# astable_555_timer_phase_1.net
KiCad netlist of a schematic drawn in EAGLE
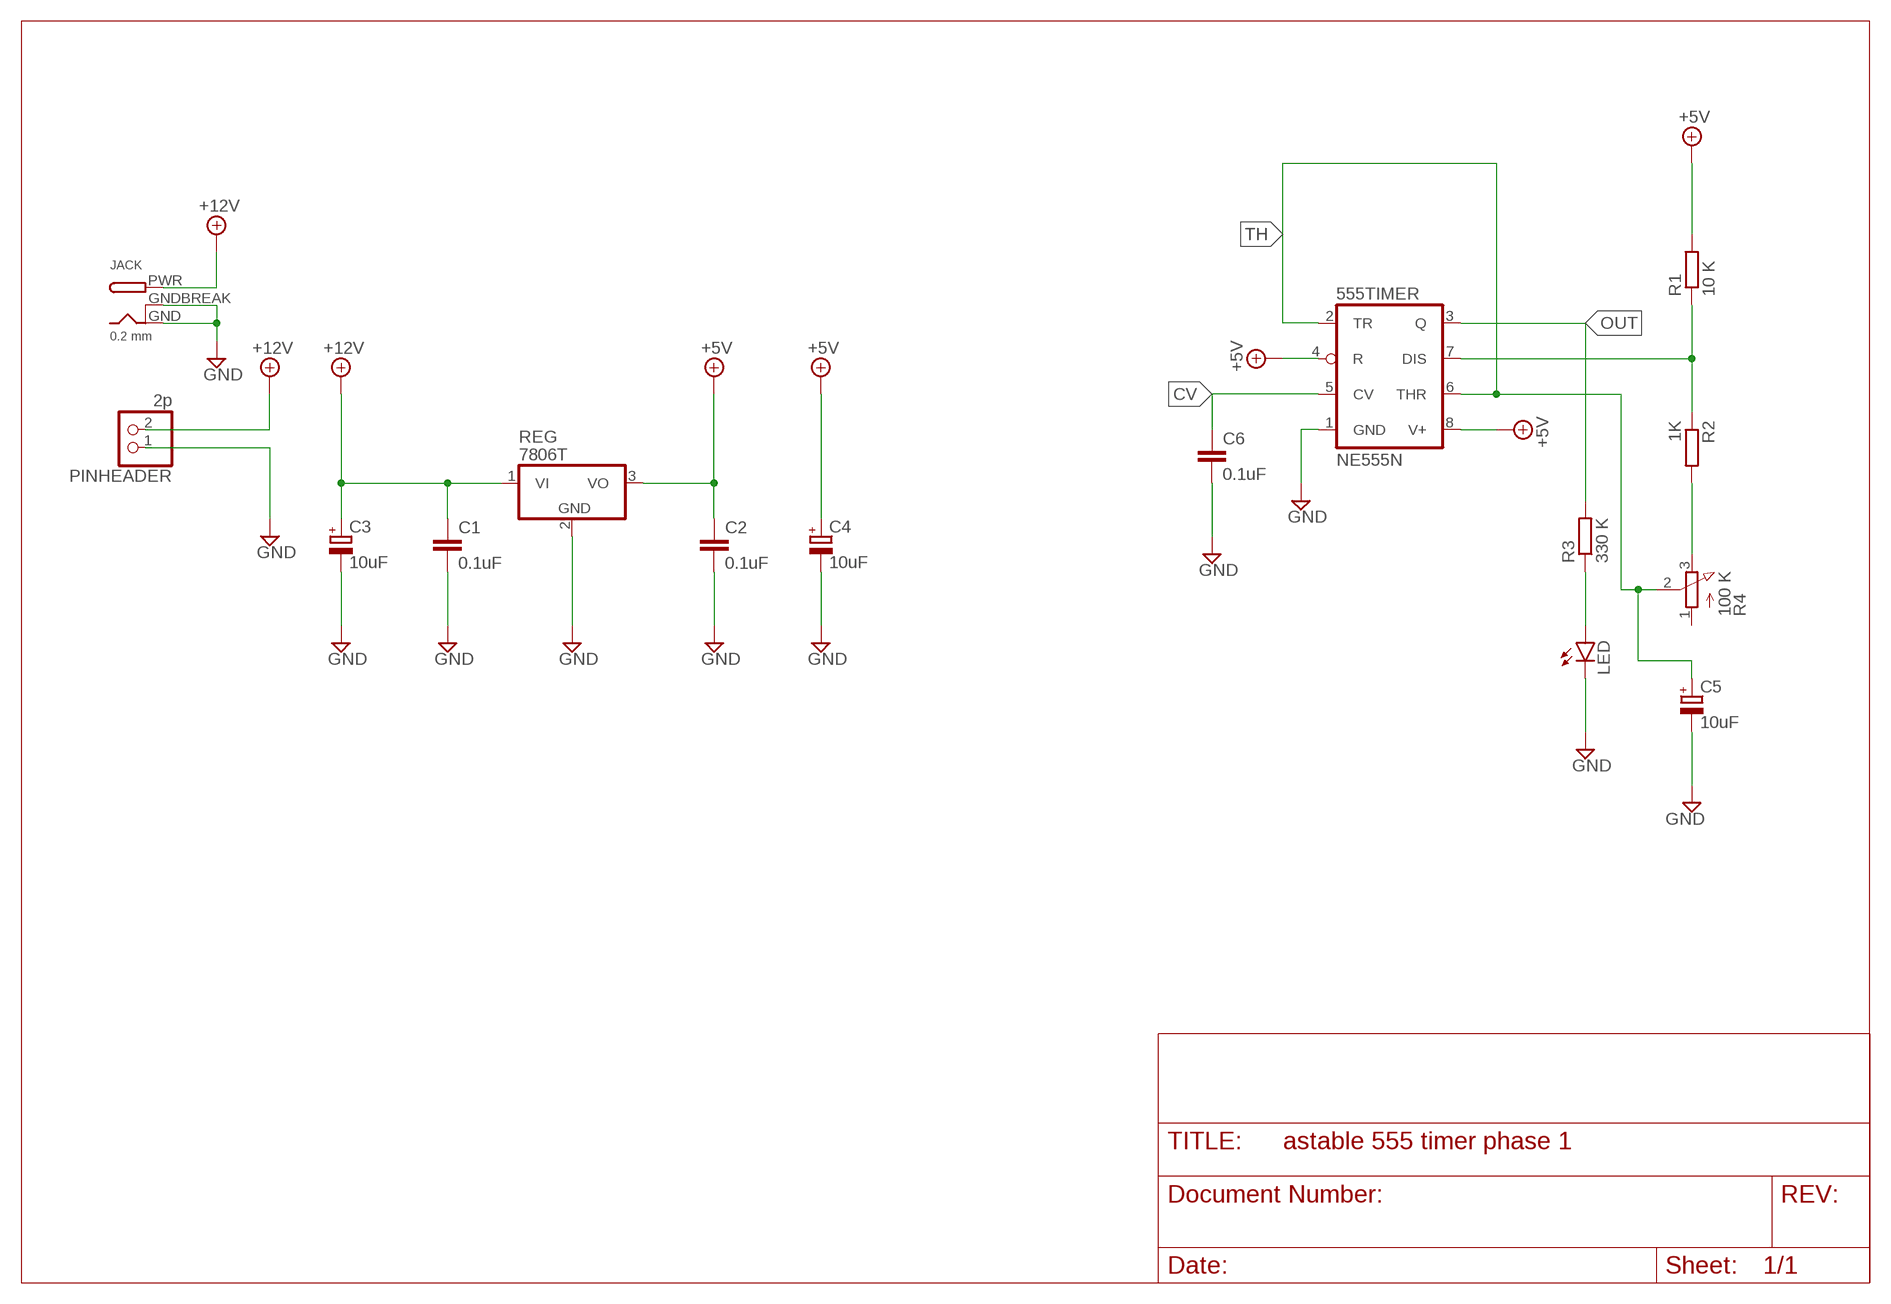
[diagram p0: schematic, sheet 1]

(export (version "E")
  (design (tool "Eeschema 10.0.6"))
  (components
    (comp (ref "555TIMER")
      (value "NE555N")
      (footprint "eagle-import:DIL08")
      (libsource (lib "eagle-import") (part "555NNE"))
    )
    (comp (ref "C1")
      (value "0.1uF")
      (footprint "eagle-import:C050-030X075")
      (libsource (lib "eagle-import") (part "C-EU050-030X075"))
    )
    (comp (ref "C2")
      (value "0.1uF")
      (footprint "eagle-import:C050-030X075")
      (libsource (lib "eagle-import") (part "C-EU050-030X075"))
    )
    (comp (ref "C3")
      (value "10uF")
      (footprint "eagle-import:E3,5-8")
      (libsource (lib "eagle-import") (part "CPOL-EUE3.5-8"))
    )
    (comp (ref "C4")
      (value "10uF")
      (footprint "eagle-import:E3,5-8")
      (libsource (lib "eagle-import") (part "CPOL-EUE3.5-8"))
    )
    (comp (ref "C5")
      (value "10uF")
      (footprint "eagle-import:E3,5-8")
      (libsource (lib "eagle-import") (part "CPOL-EUE3.5-8"))
    )
    (comp (ref "C6")
      (value "0.1uF")
      (footprint "eagle-import:C050-030X075")
      (libsource (lib "eagle-import") (part "C-EU050-030X075"))
    )
    (comp (ref "JACK")
      (value "0.2 mm")
      (footprint "eagle-import:DCJACK_2MM_PTH")
      (libsource (lib "eagle-import") (part "DCBARRELPTH"))
    )
    (comp (ref "LED")
      (value "LED5MM")
      (footprint "eagle-import:LED5MM")
      (libsource (lib "eagle-import") (part "LED5MM"))
    )
    (comp (ref "PINHEADER")
      (value "2p")
      (footprint "eagle-import:1X02")
      (libsource (lib "eagle-import") (part "PINHD-1X2"))
    )
    (comp (ref "R1")
      (value "10 K")
      (footprint "eagle-import:0207_10")
      (libsource (lib "eagle-import") (part "R-EU_0207/10"))
    )
    (comp (ref "R2")
      (value "1K")
      (footprint "eagle-import:0207_10")
      (libsource (lib "eagle-import") (part "R-EU_0207/10"))
    )
    (comp (ref "R3")
      (value "330 K")
      (footprint "eagle-import:0207_10")
      (libsource (lib "eagle-import") (part "R-EU_0207/10"))
    )
    (comp (ref "R4")
      (value "100 K")
      (footprint "eagle-import:3RP_1610N")
      (libsource (lib "eagle-import") (part "3RP/1610N"))
    )
    (comp (ref "REG")
      (value "7806T")
      (footprint "eagle-import:TO220H")
      (libsource (lib "eagle-import") (part "78T06"))
    )
  )
  (nets
    (net (code "1") (name "+5V") (class "Default")
      (node (ref "555TIMER") (pin "4") (pinfunction "R_4") (pintype "input"))
      (node (ref "555TIMER") (pin "8") (pinfunction "V+_8") (pintype "power_in"))
      (node (ref "C2") (pin "1") (pinfunction "1_1") (pintype "passive"))
      (node (ref "C4") (pin "+") (pinfunction "+_+") (pintype "passive"))
      (node (ref "R1") (pin "2") (pinfunction "2_2") (pintype "passive"))
      (node (ref "REG") (pin "3") (pinfunction "VO_3") (pintype "passive"))
    )
    (net (code "2") (name "+12V") (class "Default")
      (node (ref "C1") (pin "1") (pinfunction "1_1") (pintype "passive"))
      (node (ref "C3") (pin "+") (pinfunction "+_+") (pintype "passive"))
      (node (ref "JACK") (pin "PWR") (pinfunction "PWR_PWR") (pintype "power_in"))
      (node (ref "PINHEADER") (pin "2") (pinfunction "2_2") (pintype "passive"))
      (node (ref "REG") (pin "1") (pinfunction "VI_1") (pintype "input"))
    )
    (net (code "3") (name "CV") (class "Default")
      (node (ref "555TIMER") (pin "5") (pinfunction "CV_5") (pintype "input"))
      (node (ref "C6") (pin "1") (pinfunction "1_1") (pintype "passive"))
    )
    (net (code "4") (name "GND") (class "Default")
      (node (ref "555TIMER") (pin "1") (pinfunction "GND_1") (pintype "power_in"))
      (node (ref "C1") (pin "2") (pinfunction "2_2") (pintype "passive"))
      (node (ref "C2") (pin "2") (pinfunction "2_2") (pintype "passive"))
      (node (ref "C3") (pin "-") (pinfunction "-_-") (pintype "passive"))
      (node (ref "C4") (pin "-") (pinfunction "-_-") (pintype "passive"))
      (node (ref "C5") (pin "-") (pinfunction "-_-") (pintype "passive"))
      (node (ref "C6") (pin "2") (pinfunction "2_2") (pintype "passive"))
      (node (ref "JACK") (pin "GND") (pinfunction "GND_GND") (pintype "power_in"))
      (node (ref "JACK") (pin "GNDBREAK") (pinfunction "GNDBREAK_GNDBREAK") (pintype "power_in"))
      (node (ref "LED") (pin "K") (pinfunction "C_K") (pintype "passive"))
      (node (ref "PINHEADER") (pin "1") (pinfunction "1_1") (pintype "passive"))
      (node (ref "REG") (pin "2") (pinfunction "GND_2") (pintype "passive"))
    )
    (net (code "5") (name "Net-(555TIMER-DIS)") (class "Default")
      (node (ref "555TIMER") (pin "7") (pinfunction "DIS_7") (pintype "input"))
      (node (ref "R1") (pin "1") (pinfunction "1_1") (pintype "passive"))
      (node (ref "R2") (pin "1") (pinfunction "1_1") (pintype "passive"))
    )
    (net (code "6") (name "Net-(LED-PadA)") (class "Default")
      (node (ref "LED") (pin "A") (pinfunction "A_A") (pintype "passive"))
      (node (ref "R3") (pin "1") (pinfunction "1_1") (pintype "passive"))
    )
    (net (code "7") (name "Net-(R4-E)") (class "Default")
      (node (ref "R2") (pin "2") (pinfunction "2_2") (pintype "passive"))
      (node (ref "R4") (pin "3") (pinfunction "E_3") (pintype "passive"))
    )
    (net (code "8") (name "OUT") (class "Default")
      (node (ref "555TIMER") (pin "3") (pinfunction "Q_3") (pintype "output"))
      (node (ref "R3") (pin "2") (pinfunction "2_2") (pintype "passive"))
    )
    (net (code "9") (name "TH") (class "Default")
      (node (ref "555TIMER") (pin "2") (pinfunction "TR_2") (pintype "input"))
      (node (ref "555TIMER") (pin "6") (pinfunction "THR_6") (pintype "input"))
      (node (ref "C5") (pin "+") (pinfunction "+_+") (pintype "passive"))
      (node (ref "R4") (pin "2") (pinfunction "S_2") (pintype "passive"))
    )
    (net (code "10") (name "unconnected-(R4-A-Pad1)") (class "Default")
      (node (ref "R4") (pin "1") (pinfunction "A_1") (pintype "passive"))
    )
  )
)
